# wakerdimmer.net
KiCad netlist of a schematic drawn in Altium Designer
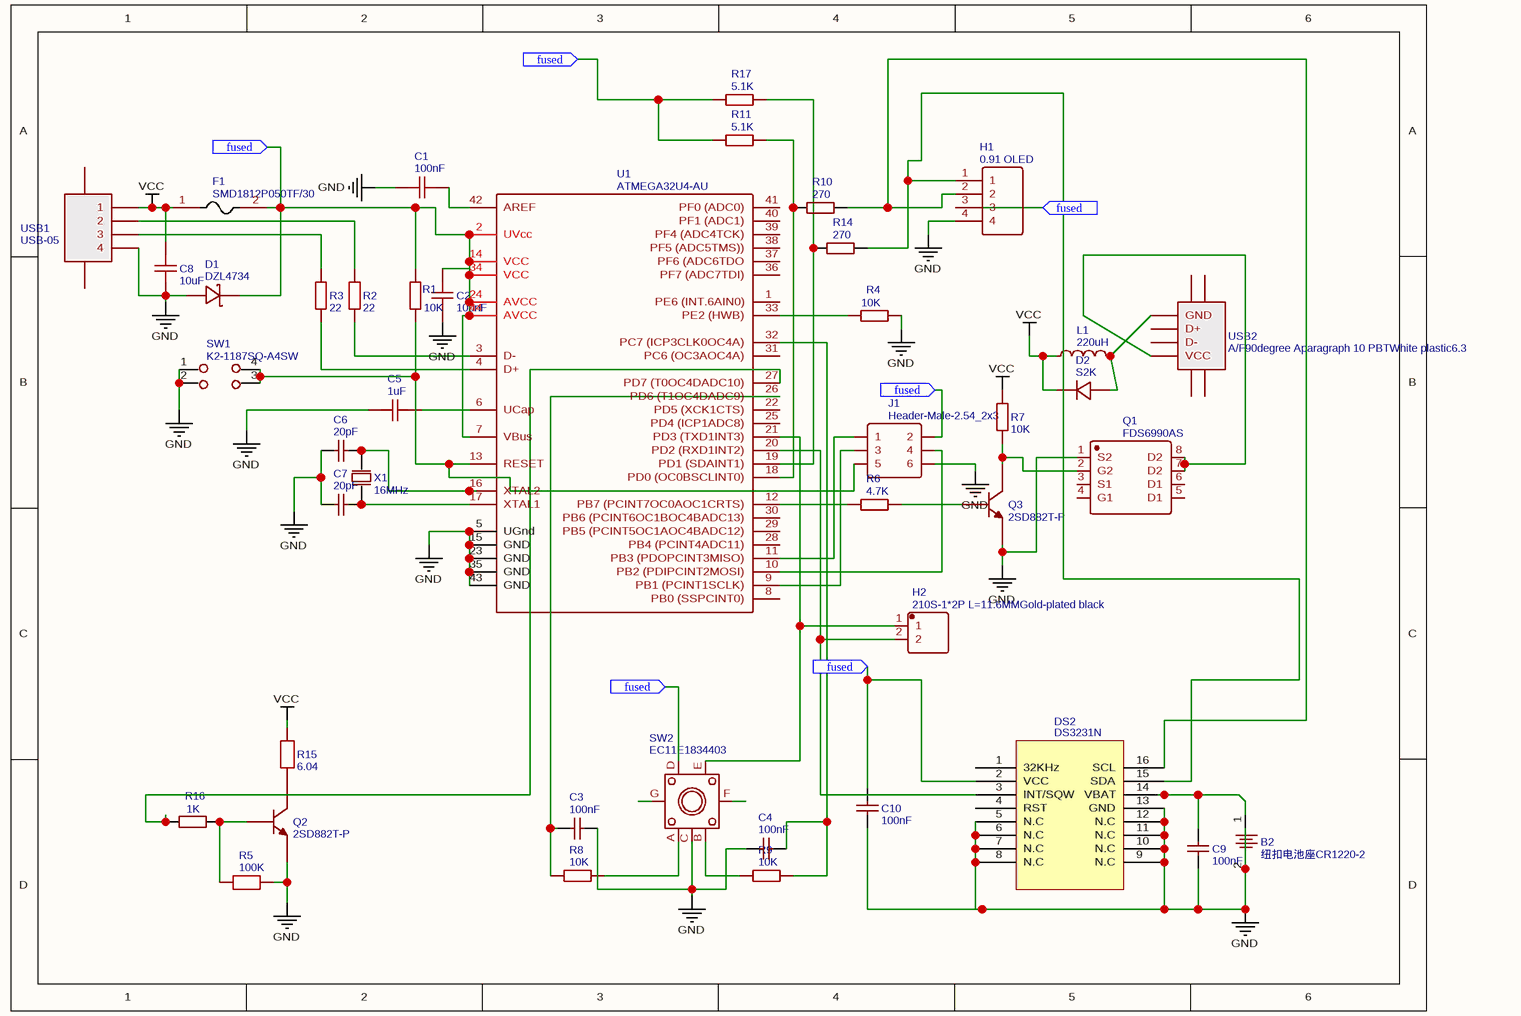
[diagram p0: wakerdimmer.schdoc]

(export (version "E")
  (design (tool "Eeschema 10.0.6"))
  (components
    (comp (ref "B2")
      (value "纽扣电池座CR1220-2")
      (fields (field (name "BOM_SUPPLIER PART") "C70381") (field (name "BOM_MANUFACTURER PART") "CR1220-2"))
      (libsource (lib "altium-import") (part "root_3_纽扣电池座CR1220-2_"))
    )
    (comp (ref "C1")
      (value "100nF")
      (fields
        (field (name "BOM_SUPPLIER PART") "C342825")
        (field (name "BOM_MANUFACTURER PART") "CGA3E3X8R1H104KT0Y0N")
        (field (name "CONTRIBUTOR") "LCSC")
      )
      (libsource (lib "altium-import") (part "root_0_100nF_"))
    )
    (comp (ref "C2")
      (value "100nF")
      (fields
        (field (name "BOM_SUPPLIER PART") "C342825")
        (field (name "BOM_MANUFACTURER PART") "CGA3E3X8R1H104KT0Y0N")
        (field (name "CONTRIBUTOR") "LCSC")
      )
      (libsource (lib "altium-import") (part "root_1_100nF_"))
    )
    (comp (ref "C3")
      (value "100nF")
      (fields
        (field (name "BOM_MANUFACTURER PART") "CT41G-0603-2X1-50V-0.1μF-K(N)")
        (field (name "BOM_SUPPLIER PART") "C125205")
        (field (name "CONTRIBUTOR") "LCSC")
      )
      (libsource (lib "") (part "root_0_100nF__1"))
    )
    (comp (ref "C4")
      (value "100nF")
      (fields
        (field (name "BOM_MANUFACTURER PART") "CT41G-0603-2X1-50V-0.1μF-K(N)")
        (field (name "BOM_SUPPLIER PART") "C125205")
        (field (name "CONTRIBUTOR") "LCSC")
      )
      (libsource (lib "") (part "root_0_100nF__1"))
    )
    (comp (ref "C5")
      (value "1uF")
      (fields
        (field (name "BOM_SUPPLIER PART") "C385891")
        (field (name "BOM_MANUFACTURER PART") "EMK105BJ105KVHF")
        (field (name "CONTRIBUTOR") "LCSC")
      )
      (libsource (lib "altium-import") (part "root_1_1uF_"))
    )
    (comp (ref "C6")
      (value "20pF")
      (fields
        (field (name "BOM_MANUFACTURER PART") "CL10C200JB8NNNC")
        (field (name "BOM_SUPPLIER PART") "C1648")
      )
      (libsource (lib "altium-import") (part "root_0_20pF_"))
    )
    (comp (ref "C7")
      (value "20pF")
      (fields
        (field (name "BOM_MANUFACTURER PART") "CL10C200JB8NNNC")
        (field (name "BOM_SUPPLIER PART") "C1648")
      )
      (libsource (lib "altium-import") (part "root_0_20pF_"))
    )
    (comp (ref "C8")
      (value "10uF")
      (fields
        (field (name "BOM_SUPPLIER PART") "C319199")
        (field (name "BOM_MANUFACTURER PART") "EMK316AB7106KL-T")
        (field (name "CONTRIBUTOR") "LCSC")
      )
      (libsource (lib "altium-import") (part "root_0_10uF_"))
    )
    (comp (ref "C9")
      (value "100nF")
      (fields
        (field (name "BOM_MANUFACTURER PART") "GRJ21BR71H104KE01L")
        (field (name "BOM_SUPPLIER PART") "C112618")
      )
      (libsource (lib "altium-import") (part "root_3_100nF_"))
    )
    (comp (ref "C10")
      (value "100nF")
      (fields
        (field (name "BOM_MANUFACTURER PART") "GRJ21BR71H104KE01L")
        (field (name "BOM_SUPPLIER PART") "C112618")
      )
      (libsource (lib "altium-import") (part "root_3_100nF_"))
    )
    (comp (ref "D1")
      (value "DZL4734")
      (fields (field (name "BOM_SUPPLIER PART") "C362311") (field (name "CONTRIBUTOR") "LCSC"))
      (libsource (lib "altium-import") (part "root_0_DZL4734_"))
    )
    (comp (ref "D2")
      (value "S2K")
      (fields (field (name "BOM_SUPPLIER PART") "C330220") (field (name "CONTRIBUTOR") "LCSC"))
      (libsource (lib "altium-import") (part "root_2_S2K_"))
    )
    (comp (ref "DS2")
      (value "DS3231N")
      (fields (field (name "BOM_MANUFACTURER PART") "?") (field (name "CONTRIBUTOR") "122089121"))
      (libsource (lib "altium-import") (part "root_0_DS3231N_"))
    )
    (comp (ref "F1")
      (value "SMD1812P050TF/30")
      (fields (field (name "BOM_SUPPLIER PART") "C12559"))
      (libsource (lib "altium-import") (part "root_0_SMD1812P050TF/30_"))
    )
    (comp (ref "H1")
      (value "0.91 OLED")
      (fields
        (field (name "BOM_MANUFACTURER PART") "220S-1*4P H=8.5MM Ytype Gold-plated")
        (field (name "BOM_SUPPLIER PART") "C124413")
        (field (name "CONTRIBUTOR") "LCSC")
      )
      (libsource (lib "altium-import") (part "root_0_0.91 OLED_"))
    )
    (comp (ref "H2")
      (value "210S-1*2P L=11.6MMGold-plated black")
      (fields (field (name "BOM_SUPPLIER PART") "C124375") (field (name "CONTRIBUTOR") "LCSC"))
      (libsource (lib "altium-import") (part "root_0_210S-1*2P L=11.6MMGold-plated black_"))
    )
    (comp (ref "J1")
      (value "Header-Male-2.54_2x3")
      (fields (field (name "BOM_SUPPLIER PART") "C65114"))
      (libsource (lib "altium-import") (part "root_0_Header-Male-2.54_2x3_"))
    )
    (comp (ref "L1")
      (value "220uH")
      (fields
        (field (name "BOM_SUPPLIER PART") "C187417")
        (field (name "BOM_MANUFACTURER PART") "ASPI-1306T-221M-T")
        (field (name "CONTRIBUTOR") "LCSC")
      )
      (libsource (lib "altium-import") (part "root_0_220uH_"))
    )
    (comp (ref "Q1")
      (value "FDS6990AS")
      (fields (field (name "BOM_SUPPLIER PART") "C51459"))
      (libsource (lib "altium-import") (part "root_0_FDS6990AS_"))
    )
    (comp (ref "Q2")
      (value "2SD882T-P")
      (fields (field (name "BOM_SUPPLIER PART") "C305479") (field (name "CONTRIBUTOR") "LCSC"))
      (libsource (lib "altium-import") (part "root_0_2SD882T-P_"))
    )
    (comp (ref "Q3")
      (value "2SD882T-P")
      (fields (field (name "BOM_SUPPLIER PART") "C305479") (field (name "CONTRIBUTOR") "LCSC"))
      (libsource (lib "altium-import") (part "root_0_2SD882T-P_"))
    )
    (comp (ref "R1")
      (value "10K")
      (fields
        (field (name "BOM_SUPPLIER PART") "C238881")
        (field (name "BOM_MANUFACTURER PART") "RMCF0603JT10K0")
        (field (name "CONTRIBUTOR") "LCSC")
      )
      (libsource (lib "altium-import") (part "root_1_10K_"))
    )
    (comp (ref "R2")
      (value "22")
      (fields
        (field (name "BOM_SUPPLIER PART") "C365407")
        (field (name "BOM_MANUFACTURER PART") "ETCR0603F22R0K9")
        (field (name "CONTRIBUTOR") "LCSC")
      )
      (libsource (lib "altium-import") (part "root_1_22_"))
    )
    (comp (ref "R3")
      (value "22")
      (fields
        (field (name "BOM_SUPPLIER PART") "C365407")
        (field (name "BOM_MANUFACTURER PART") "ETCR0603F22R0K9")
        (field (name "CONTRIBUTOR") "LCSC")
      )
      (libsource (lib "altium-import") (part "root_1_22_"))
    )
    (comp (ref "R4")
      (value "10K")
      (fields
        (field (name "BOM_SUPPLIER PART") "C238881")
        (field (name "BOM_MANUFACTURER PART") "RMCF0603JT10K0")
        (field (name "CONTRIBUTOR") "LCSC")
      )
      (libsource (lib "altium-import") (part "root_0_10K_"))
    )
    (comp (ref "R5")
      (value "100K")
      (fields
        (field (name "BOM_SUPPLIER PART") "C394537")
        (field (name "BOM_MANUFACTURER PART") "PTFR0603B100KN9")
        (field (name "CONTRIBUTOR") "LCSC")
      )
      (libsource (lib "altium-import") (part "root_0_100K_"))
    )
    (comp (ref "R6")
      (value "4.7K")
      (fields
        (field (name "BOM_SUPPLIER PART") "C269713")
        (field (name "BOM_MANUFACTURER PART") "RMC06034.7K1%N")
        (field (name "CONTRIBUTOR") "LCSC")
      )
      (libsource (lib "altium-import") (part "root_0_4.7K_"))
    )
    (comp (ref "R7")
      (value "10K")
      (fields
        (field (name "BOM_SUPPLIER PART") "C238881")
        (field (name "BOM_MANUFACTURER PART") "RMCF0603JT10K0")
        (field (name "CONTRIBUTOR") "LCSC")
      )
      (libsource (lib "altium-import") (part "root_1_10K_"))
    )
    (comp (ref "R8")
      (value "10K")
      (fields
        (field (name "BOM_SUPPLIER PART") "C238881")
        (field (name "BOM_MANUFACTURER PART") "RMCF0603JT10K0")
        (field (name "CONTRIBUTOR") "LCSC")
      )
      (libsource (lib "altium-import") (part "root_0_10K_"))
    )
    (comp (ref "R9")
      (value "10K")
      (fields
        (field (name "BOM_SUPPLIER PART") "C238881")
        (field (name "BOM_MANUFACTURER PART") "RMCF0603JT10K0")
        (field (name "CONTRIBUTOR") "LCSC")
      )
      (libsource (lib "altium-import") (part "root_0_10K_"))
    )
    (comp (ref "R10")
      (value "270")
      (fields
        (field (name "BOM_MANUFACTURER PART") "0603WAJ0271T5E")
        (field (name "BOM_SUPPLIER PART") "C25223")
      )
      (libsource (lib "altium-import") (part "root_0_270_"))
    )
    (comp (ref "R11")
      (value "5.1K")
      (fields
        (field (name "BOM_SUPPLIER PART") "C269716")
        (field (name "BOM_MANUFACTURER PART") "RMC06035.1K1%N")
        (field (name "CONTRIBUTOR") "LCSC")
      )
      (libsource (lib "altium-import") (part "root_0_5.1K_"))
    )
    (comp (ref "R14")
      (value "270")
      (fields
        (field (name "BOM_MANUFACTURER PART") "0603WAJ0271T5E")
        (field (name "BOM_SUPPLIER PART") "C25223")
      )
      (libsource (lib "altium-import") (part "root_0_270_"))
    )
    (comp (ref "R15")
      (value "6.04")
      (fields
        (field (name "BOM_SUPPLIER PART") "C368086")
        (field (name "BOM_MANUFACTURER PART") "WR12W6R04FTL")
        (field (name "CONTRIBUTOR") "LCSC")
      )
      (libsource (lib "altium-import") (part "root_1_6.04_"))
    )
    (comp (ref "R16")
      (value "1K")
      (fields
        (field (name "BOM_MANUFACTURER PART") "0603WAF1001T5E")
        (field (name "BOM_SUPPLIER PART") "C21190")
      )
      (libsource (lib "altium-import") (part "root_0_1K_"))
    )
    (comp (ref "R17")
      (value "5.1K")
      (fields
        (field (name "BOM_SUPPLIER PART") "C269716")
        (field (name "BOM_MANUFACTURER PART") "RMC06035.1K1%N")
        (field (name "CONTRIBUTOR") "LCSC")
      )
      (libsource (lib "altium-import") (part "root_0_5.1K_"))
    )
    (comp (ref "SW1")
      (value "K2-1187SQ-A4SW")
      (fields (field (name "BOM_SUPPLIER PART") "C92584"))
      (libsource (lib "altium-import") (part "root_0_K2-1187SQ-A4SW_"))
    )
    (comp (ref "SW2")
      (value "EC11E1834403")
      (fields (field (name "BOM_SUPPLIER PART") "C361165") (field (name "CONTRIBUTOR") "LCSC"))
      (libsource (lib "altium-import") (part "root_0_EC11E1834403_"))
    )
    (comp (ref "U1")
      (value "ATMEGA32U4-AU")
      (fields (field (name "BOM_SUPPLIER PART") "C44854"))
      (libsource (lib "altium-import") (part "root_0_ATMEGA32U4-AU_"))
    )
    (comp (ref "USB1")
      (value "USB-05")
      (fields (field (name "BOM_SUPPLIER PART") "C112454") (field (name "CONTRIBUTOR") "LCSC"))
      (libsource (lib "altium-import") (part "root_0_USB-05_"))
    )
    (comp (ref "USB2")
      (value "A/F90degree Aparagraph 10 PBTWhite plastic6.3")
      (fields (field (name "BOM_SUPPLIER PART") "C42576"))
      (libsource (lib "altium-import") (part "root_2_A/F90degree Aparagraph 10 PBTWhite plastic6.3_"))
    )
    (comp (ref "X1")
      (value "16MHz")
      (fields
        (field (name "BOM_MANUFACTURER PART") "X49SD16MSD2SC")
        (field (name "BOM_SUPPLIER PART") "C16212")
      )
      (libsource (lib "altium-import") (part "root_1_16MHz_"))
    )
  )
  (nets
    (net (code "1") (name "/fused") (class "Default")
      (node (ref "C10") (pin "1") (pinfunction "1_1") (pintype "passive"))
      (node (ref "C2") (pin "2") (pinfunction "2_2") (pintype "passive"))
      (node (ref "D1") (pin "2") (pinfunction "K_2") (pintype "passive"))
      (node (ref "DS2") (pin "2") (pinfunction "VCC_2") (pintype "passive"))
      (node (ref "F1") (pin "2") (pinfunction "2_2") (pintype "passive"))
      (node (ref "H1") (pin "3") (pinfunction "3_3") (pintype "passive"))
      (node (ref "J1") (pin "2") (pinfunction "2_2") (pintype "passive"))
      (node (ref "R1") (pin "2") (pinfunction "2_2") (pintype "passive"))
      (node (ref "R11") (pin "1") (pinfunction "1_1") (pintype "passive"))
      (node (ref "R17") (pin "1") (pinfunction "1_1") (pintype "passive"))
      (node (ref "SW2") (pin "D") (pinfunction "D_D") (pintype "passive"))
      (node (ref "U1") (pin "14") (pinfunction "VCC_14") (pintype "passive"))
      (node (ref "U1") (pin "2") (pinfunction "UVcc_2") (pintype "passive"))
      (node (ref "U1") (pin "24") (pinfunction "AVCC_24") (pintype "passive"))
      (node (ref "U1") (pin "34") (pinfunction "VCC_34") (pintype "passive"))
      (node (ref "U1") (pin "44") (pinfunction "AVCC_44") (pintype "passive"))
      (node (ref "U1") (pin "7") (pinfunction "VBus_7") (pintype "passive"))
    )
    (net (code "2") (name "GND") (class "Default")
      (node (ref "B2") (pin "2") (pinfunction "2_2") (pintype "passive"))
      (node (ref "C1") (pin "1") (pinfunction "1_1") (pintype "passive"))
      (node (ref "C10") (pin "2") (pinfunction "2_2") (pintype "passive"))
      (node (ref "C2") (pin "1") (pinfunction "1_1") (pintype "passive"))
      (node (ref "C3") (pin "2") (pinfunction "2_2") (pintype "passive"))
      (node (ref "C4") (pin "1") (pinfunction "1_1") (pintype "passive"))
      (node (ref "C5") (pin "2") (pinfunction "2_2") (pintype "passive"))
      (node (ref "C6") (pin "1") (pinfunction "1_1") (pintype "passive"))
      (node (ref "C7") (pin "1") (pinfunction "1_1") (pintype "passive"))
      (node (ref "C8") (pin "1") (pinfunction "1_1") (pintype "passive"))
      (node (ref "C9") (pin "2") (pinfunction "2_2") (pintype "passive"))
      (node (ref "D1") (pin "1") (pinfunction "A_1") (pintype "passive"))
      (node (ref "DS2") (pin "10") (pinfunction "N.C_10") (pintype "passive"))
      (node (ref "DS2") (pin "11") (pinfunction "N.C_11") (pintype "passive"))
      (node (ref "DS2") (pin "12") (pinfunction "N.C_12") (pintype "passive"))
      (node (ref "DS2") (pin "13") (pinfunction "GND_13") (pintype "passive"))
      (node (ref "DS2") (pin "5") (pinfunction "N.C_5") (pintype "passive"))
      (node (ref "DS2") (pin "6") (pinfunction "N.C_6") (pintype "passive"))
      (node (ref "DS2") (pin "7") (pinfunction "N.C_7") (pintype "passive"))
      (node (ref "DS2") (pin "8") (pinfunction "N.C_8") (pintype "passive"))
      (node (ref "DS2") (pin "9") (pinfunction "N.C_9") (pintype "passive"))
      (node (ref "H1") (pin "4") (pinfunction "4_4") (pintype "passive"))
      (node (ref "J1") (pin "6") (pinfunction "6_6") (pintype "passive"))
      (node (ref "Q1") (pin "1") (pinfunction "S2_1") (pintype "passive"))
      (node (ref "Q2") (pin "3") (pinfunction "E_3") (pintype "passive"))
      (node (ref "Q3") (pin "3") (pinfunction "E_3") (pintype "passive"))
      (node (ref "R4") (pin "2") (pinfunction "2_2") (pintype "passive"))
      (node (ref "R5") (pin "2") (pinfunction "2_2") (pintype "passive"))
      (node (ref "SW1") (pin "1") (pinfunction "1_1") (pintype "passive"))
      (node (ref "SW1") (pin "2") (pinfunction "2_2") (pintype "passive"))
      (node (ref "SW2") (pin "C") (pinfunction "C_C") (pintype "passive"))
      (node (ref "U1") (pin "15") (pinfunction "GND_15") (pintype "passive"))
      (node (ref "U1") (pin "23") (pinfunction "GND_23") (pintype "passive"))
      (node (ref "U1") (pin "35") (pinfunction "GND_35") (pintype "passive"))
      (node (ref "U1") (pin "43") (pinfunction "GND_43") (pintype "passive"))
      (node (ref "U1") (pin "5") (pinfunction "UGnd_5") (pintype "passive"))
      (node (ref "USB1") (pin "4") (pinfunction "4_4") (pintype "passive"))
    )
    (net (code "3") (name "Net-(DS2-INT{slash}SQW)") (class "Default")
      (node (ref "DS2") (pin "3") (pinfunction "INT/SQW_3") (pintype "passive"))
      (node (ref "H2") (pin "2") (pinfunction "2_2") (pintype "passive"))
      (node (ref "U1") (pin "20") (pinfunction "PD2_(RXD1INT2)_20") (pintype "passive"))
    )
    (net (code "4") (name "Net-(DS2-SCL)") (class "Default")
      (node (ref "DS2") (pin "16") (pinfunction "SCL_16") (pintype "passive"))
      (node (ref "H1") (pin "2") (pinfunction "2_2") (pintype "passive"))
      (node (ref "R10") (pin "2") (pinfunction "2_2") (pintype "passive"))
    )
    (net (code "5") (name "Net-(DS2-SDA)") (class "Default")
      (node (ref "DS2") (pin "15") (pinfunction "SDA_15") (pintype "passive"))
      (node (ref "H1") (pin "1") (pinfunction "1_1") (pintype "passive"))
      (node (ref "R14") (pin "2") (pinfunction "2_2") (pintype "passive"))
    )
    (net (code "6") (name "Net-(DS2-VBAT)") (class "Default")
      (node (ref "B2") (pin "1") (pinfunction "1_1") (pintype "passive"))
      (node (ref "C9") (pin "1") (pinfunction "1_1") (pintype "passive"))
      (node (ref "DS2") (pin "14") (pinfunction "VBAT_14") (pintype "passive"))
    )
    (net (code "7") (name "Net-(Q1-G2)") (class "Default")
      (node (ref "Q1") (pin "2") (pinfunction "G2_2") (pintype "passive"))
      (node (ref "Q3") (pin "2") (pinfunction "C_2") (pintype "passive"))
      (node (ref "R7") (pin "1") (pinfunction "1_1") (pintype "passive"))
    )
    (net (code "8") (name "Net-(Q2-B)") (class "Default")
      (node (ref "Q2") (pin "1") (pinfunction "B_1") (pintype "passive"))
      (node (ref "R16") (pin "2") (pinfunction "2_2") (pintype "passive"))
      (node (ref "R5") (pin "1") (pinfunction "1_1") (pintype "passive"))
    )
    (net (code "9") (name "Net-(Q2-C)") (class "Default")
      (node (ref "Q2") (pin "2") (pinfunction "C_2") (pintype "passive"))
      (node (ref "R15") (pin "1") (pinfunction "1_1") (pintype "passive"))
    )
    (net (code "10") (name "Net-(Q3-B)") (class "Default")
      (node (ref "Q3") (pin "1") (pinfunction "B_1") (pintype "passive"))
      (node (ref "R6") (pin "2") (pinfunction "2_2") (pintype "passive"))
    )
    (net (code "11") (name "Net-(R2-Pad2)") (class "Default")
      (node (ref "R2") (pin "2") (pinfunction "2_2") (pintype "passive"))
      (node (ref "USB1") (pin "2") (pinfunction "2_2") (pintype "passive"))
    )
    (net (code "12") (name "Net-(R3-Pad2)") (class "Default")
      (node (ref "R3") (pin "2") (pinfunction "2_2") (pintype "passive"))
      (node (ref "USB1") (pin "3") (pinfunction "3_3") (pintype "passive"))
    )
    (net (code "13") (name "Net-(R8-Pad2)") (class "Default")
      (node (ref "R8") (pin "2") (pinfunction "2_2") (pintype "passive"))
      (node (ref "SW2") (pin "A") (pinfunction "A_A") (pintype "passive"))
    )
    (net (code "14") (name "Net-(R9-Pad1)") (class "Default")
      (node (ref "R9") (pin "1") (pinfunction "1_1") (pintype "passive"))
      (node (ref "SW2") (pin "B") (pinfunction "B_B") (pintype "passive"))
    )
    (net (code "15") (name "Net-(U1-AREF)") (class "Default")
      (node (ref "C1") (pin "2") (pinfunction "2_2") (pintype "passive"))
      (node (ref "U1") (pin "42") (pinfunction "AREF_42") (pintype "passive"))
    )
    (net (code "16") (name "Net-(U1-D+)") (class "Default")
      (node (ref "R3") (pin "1") (pinfunction "1_1") (pintype "passive"))
      (node (ref "U1") (pin "4") (pinfunction "D+_4") (pintype "passive"))
    )
    (net (code "17") (name "Net-(U1-D-)") (class "Default")
      (node (ref "R2") (pin "1") (pinfunction "1_1") (pintype "passive"))
      (node (ref "U1") (pin "3") (pinfunction "D-_3") (pintype "passive"))
    )
    (net (code "18") (name "Net-(U1-PB1_(PCINT1SCLK))") (class "Default")
      (node (ref "J1") (pin "3") (pinfunction "3_3") (pintype "passive"))
      (node (ref "U1") (pin "9") (pinfunction "PB1_(PCINT1SCLK)_9") (pintype "passive"))
    )
    (net (code "19") (name "Net-(U1-PB2_(PDIPCINT2MOSI))") (class "Default")
      (node (ref "J1") (pin "4") (pinfunction "4_4") (pintype "passive"))
      (node (ref "U1") (pin "10") (pinfunction "PB2_(PDIPCINT2MOSI)_10") (pintype "passive"))
    )
    (net (code "20") (name "Net-(U1-PB3_(PDOPCINT3MISO))") (class "Default")
      (node (ref "J1") (pin "1") (pinfunction "1_1") (pintype "passive"))
      (node (ref "U1") (pin "11") (pinfunction "PB3_(PDOPCINT3MISO)_11") (pintype "passive"))
    )
    (net (code "21") (name "Net-(U1-PB7_(PCINT7OC0AOC1CRTS))") (class "Default")
      (node (ref "R6") (pin "1") (pinfunction "1_1") (pintype "passive"))
      (node (ref "U1") (pin "12") (pinfunction "PB7_(PCINT7OC0AOC1CRTS)_12") (pintype "passive"))
    )
    (net (code "22") (name "Net-(U1-PC7_(ICP3CLK0OC4A))") (class "Default")
      (node (ref "C4") (pin "2") (pinfunction "2_2") (pintype "passive"))
      (node (ref "R9") (pin "2") (pinfunction "2_2") (pintype "passive"))
      (node (ref "U1") (pin "32") (pinfunction "PC7_(ICP3CLK0OC4A)_32") (pintype "passive"))
    )
    (net (code "23") (name "Net-(U1-PD0_(OC0BSCLINT0))") (class "Default")
      (node (ref "R10") (pin "1") (pinfunction "1_1") (pintype "passive"))
      (node (ref "R11") (pin "2") (pinfunction "2_2") (pintype "passive"))
      (node (ref "U1") (pin "18") (pinfunction "PD0_(OC0BSCLINT0)_18") (pintype "passive"))
    )
    (net (code "24") (name "Net-(U1-PD1_(SDAINT1))") (class "Default")
      (node (ref "R14") (pin "1") (pinfunction "1_1") (pintype "passive"))
      (node (ref "R17") (pin "2") (pinfunction "2_2") (pintype "passive"))
      (node (ref "U1") (pin "19") (pinfunction "PD1_(SDAINT1)_19") (pintype "passive"))
    )
    (net (code "25") (name "Net-(U1-PD3_(TXD1INT3))") (class "Default")
      (node (ref "H2") (pin "1") (pinfunction "1_1") (pintype "passive"))
      (node (ref "SW2") (pin "E") (pinfunction "E_E") (pintype "passive"))
      (node (ref "U1") (pin "21") (pinfunction "PD3_(TXD1INT3)_21") (pintype "passive"))
    )
    (net (code "26") (name "Net-(U1-PD6_(T1OC4DADC9))") (class "Default")
      (node (ref "C3") (pin "1") (pinfunction "1_1") (pintype "passive"))
      (node (ref "R8") (pin "1") (pinfunction "1_1") (pintype "passive"))
      (node (ref "U1") (pin "26") (pinfunction "PD6_(T1OC4DADC9)_26") (pintype "passive"))
    )
    (net (code "27") (name "Net-(U1-PD7_(T0OC4DADC10))") (class "Default")
      (node (ref "R16") (pin "1") (pinfunction "1_1") (pintype "passive"))
      (node (ref "U1") (pin "27") (pinfunction "PD7_(T0OC4DADC10)_27") (pintype "passive"))
    )
    (net (code "28") (name "Net-(U1-PE2_(HWB))") (class "Default")
      (node (ref "R4") (pin "1") (pinfunction "1_1") (pintype "passive"))
      (node (ref "U1") (pin "33") (pinfunction "PE2_(HWB)_33") (pintype "passive"))
    )
    (net (code "29") (name "Net-(U1-RESET)") (class "Default")
      (node (ref "J1") (pin "5") (pinfunction "5_5") (pintype "passive"))
      (node (ref "R1") (pin "1") (pinfunction "1_1") (pintype "passive"))
      (node (ref "SW1") (pin "3") (pinfunction "3_3") (pintype "passive"))
      (node (ref "SW1") (pin "4") (pinfunction "4_4") (pintype "passive"))
      (node (ref "U1") (pin "13") (pinfunction "RESET_13") (pintype "passive"))
    )
    (net (code "30") (name "Net-(U1-UCap)") (class "Default")
      (node (ref "C5") (pin "1") (pinfunction "1_1") (pintype "passive"))
      (node (ref "U1") (pin "6") (pinfunction "UCap_6") (pintype "passive"))
    )
    (net (code "31") (name "Net-(U1-XTAL1)") (class "Default")
      (node (ref "C7") (pin "2") (pinfunction "2_2") (pintype "passive"))
      (node (ref "U1") (pin "17") (pinfunction "XTAL1_17") (pintype "passive"))
      (node (ref "X1") (pin "2") (pinfunction "OSC2_2") (pintype "passive"))
    )
    (net (code "32") (name "Net-(U1-XTAL2)") (class "Default")
      (node (ref "C6") (pin "2") (pinfunction "2_2") (pintype "passive"))
      (node (ref "U1") (pin "16") (pinfunction "XTAL2_16") (pintype "passive"))
      (node (ref "X1") (pin "1") (pinfunction "OSC1_1") (pintype "passive"))
    )
    (net (code "33") (name "Net-(USB2-GND)") (class "Default")
      (node (ref "D2") (pin "1") (pinfunction "1_1") (pintype "passive"))
      (node (ref "L1") (pin "2") (pinfunction "2_2") (pintype "passive"))
      (node (ref "USB2") (pin "4") (pinfunction "GND_4") (pintype "passive"))
    )
    (net (code "34") (name "Net-(USB2-VCC)") (class "Default")
      (node (ref "Q1") (pin "7") (pinfunction "D2_7") (pintype "passive"))
      (node (ref "Q1") (pin "8") (pinfunction "D2_8") (pintype "passive"))
      (node (ref "USB2") (pin "1") (pinfunction "VCC_1") (pintype "passive"))
    )
    (net (code "35") (name "VCC") (class "Default")
      (node (ref "C8") (pin "2") (pinfunction "2_2") (pintype "passive"))
      (node (ref "D2") (pin "2") (pinfunction "2_2") (pintype "passive"))
      (node (ref "F1") (pin "1") (pinfunction "1_1") (pintype "passive"))
      (node (ref "L1") (pin "1") (pinfunction "1_1") (pintype "passive"))
      (node (ref "R15") (pin "2") (pinfunction "2_2") (pintype "passive"))
      (node (ref "R7") (pin "2") (pinfunction "2_2") (pintype "passive"))
      (node (ref "USB1") (pin "1") (pinfunction "1_1") (pintype "passive"))
    )
    (net (code "36") (name "unconnected-(DS2-32KHz-Pad1)") (class "Default")
      (node (ref "DS2") (pin "1") (pinfunction "32KHz_1") (pintype "passive"))
    )
    (net (code "37") (name "unconnected-(DS2-RST-Pad4)") (class "Default")
      (node (ref "DS2") (pin "4") (pinfunction "RST_4") (pintype "passive"))
    )
    (net (code "38") (name "unconnected-(Q1-D1-Pad5)") (class "Default")
      (node (ref "Q1") (pin "5") (pinfunction "D1_5") (pintype "passive"))
    )
    (net (code "39") (name "unconnected-(Q1-D1-Pad6)") (class "Default")
      (node (ref "Q1") (pin "6") (pinfunction "D1_6") (pintype "passive"))
    )
    (net (code "40") (name "unconnected-(Q1-G1-Pad4)") (class "Default")
      (node (ref "Q1") (pin "4") (pinfunction "G1_4") (pintype "passive"))
    )
    (net (code "41") (name "unconnected-(Q1-S1-Pad3)") (class "Default")
      (node (ref "Q1") (pin "3") (pinfunction "S1_3") (pintype "passive"))
    )
    (net (code "42") (name "unconnected-(SW2-PadF)") (class "Default")
      (node (ref "SW2") (pin "F") (pinfunction "F_F") (pintype "passive"))
    )
    (net (code "43") (name "unconnected-(SW2-PadG)") (class "Default")
      (node (ref "SW2") (pin "G") (pinfunction "G_G") (pintype "passive"))
    )
    (net (code "44") (name "unconnected-(U1-PB0_(SSPCINT0)-Pad8)") (class "Default")
      (node (ref "U1") (pin "8") (pinfunction "PB0_(SSPCINT0)_8") (pintype "passive"))
    )
    (net (code "45") (name "unconnected-(U1-PB4_(PCINT4ADC11)-Pad28)") (class "Default")
      (node (ref "U1") (pin "28") (pinfunction "PB4_(PCINT4ADC11)_28") (pintype "passive"))
    )
    (net (code "46") (name "unconnected-(U1-PB5_(PCINT5OC1AOC4BADC12)-Pad29)") (class "Default")
      (node (ref "U1") (pin "29") (pinfunction "PB5_(PCINT5OC1AOC4BADC12)_29") (pintype "passive"))
    )
    (net (code "47") (name "unconnected-(U1-PB6_(PCINT6OC1BOC4BADC13)-Pad30)") (class "Default")
      (node (ref "U1") (pin "30") (pinfunction "PB6_(PCINT6OC1BOC4BADC13)_30") (pintype "passive"))
    )
    (net (code "48") (name "unconnected-(U1-PC6_(OC3AOC4A)-Pad31)") (class "Default")
      (node (ref "U1") (pin "31") (pinfunction "PC6_(OC3AOC4A)_31") (pintype "passive"))
    )
    (net (code "49") (name "unconnected-(U1-PD4_(ICP1ADC8)-Pad25)") (class "Default")
      (node (ref "U1") (pin "25") (pinfunction "PD4_(ICP1ADC8)_25") (pintype "passive"))
    )
    (net (code "50") (name "unconnected-(U1-PD5_(XCK1CTS)-Pad22)") (class "Default")
      (node (ref "U1") (pin "22") (pinfunction "PD5_(XCK1CTS)_22") (pintype "passive"))
    )
    (net (code "51") (name "unconnected-(U1-PE6_(INT.6AIN0)-Pad1)") (class "Default")
      (node (ref "U1") (pin "1") (pinfunction "PE6_(INT.6AIN0)_1") (pintype "passive"))
    )
    (net (code "52") (name "unconnected-(U1-PF0_(ADC0)-Pad41)") (class "Default")
      (node (ref "U1") (pin "41") (pinfunction "PF0_(ADC0)_41") (pintype "passive"))
    )
    (net (code "53") (name "unconnected-(U1-PF1_(ADC1)-Pad40)") (class "Default")
      (node (ref "U1") (pin "40") (pinfunction "PF1_(ADC1)_40") (pintype "passive"))
    )
    (net (code "54") (name "unconnected-(U1-PF4_(ADC4TCK)-Pad39)") (class "Default")
      (node (ref "U1") (pin "39") (pinfunction "PF4_(ADC4TCK)_39") (pintype "passive"))
    )
    (net (code "55") (name "unconnected-(U1-PF5_(ADC5TMS))-Pad38)") (class "Default")
      (node (ref "U1") (pin "38") (pinfunction "PF5_(ADC5TMS))_38") (pintype "passive"))
    )
    (net (code "56") (name "unconnected-(U1-PF6_(ADC6TDO-Pad37)") (class "Default")
      (node (ref "U1") (pin "37") (pinfunction "PF6_(ADC6TDO_37") (pintype "passive"))
    )
    (net (code "57") (name "unconnected-(U1-PF7_(ADC7TDI)-Pad36)") (class "Default")
      (node (ref "U1") (pin "36") (pinfunction "PF7_(ADC7TDI)_36") (pintype "passive"))
    )
    (net (code "58") (name "unconnected-(USB1-Pad0)") (class "Default")
      (node (ref "USB1") (pin "0") (pinfunction "0_0") (pintype "passive"))
    )
    (net (code "59") (name "unconnected-(USB1-Pad6)") (class "Default")
      (node (ref "USB1") (pin "6") (pinfunction "6_6") (pintype "passive"))
    )
    (net (code "60") (name "unconnected-(USB2-D+-Pad3)") (class "Default")
      (node (ref "USB2") (pin "3") (pinfunction "D+_3") (pintype "passive"))
    )
    (net (code "61") (name "unconnected-(USB2-D--Pad2)") (class "Default")
      (node (ref "USB2") (pin "2") (pinfunction "D-_2") (pintype "passive"))
    )
    (net (code "62") (name "unconnected-(USB2-Pad0)") (class "Default")
      (node (ref "USB2") (pin "0") (pinfunction "0_0") (pintype "passive"))
    )
    (net (code "63") (name "unconnected-(USB2-Pad0)_1") (class "Default")
      (node (ref "USB2") (pin "0") (pinfunction "0_0") (pintype "passive"))
    )
    (net (code "64") (name "unconnected-(USB2-Pad0)_2") (class "Default")
      (node (ref "USB2") (pin "0") (pinfunction "0_0") (pintype "passive"))
    )
    (net (code "65") (name "unconnected-(USB2-Pad0)_3") (class "Default")
      (node (ref "USB2") (pin "0") (pinfunction "0_0") (pintype "passive"))
    )
  )
)
